# ark.net
KiCad netlist of a schematic drawn in Altium Designer
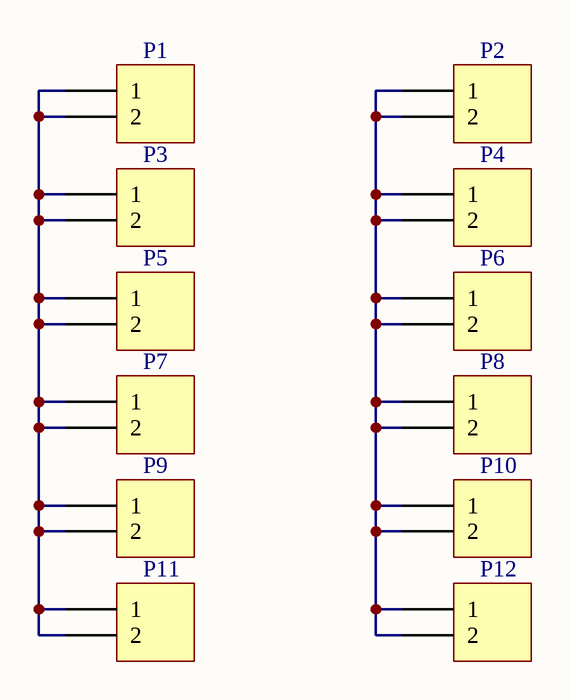
[diagram p0: ark.SchDoc]

(export (version "E")
  (design (tool "Eeschema 10.0.6"))
  (components
    (comp (ref "P1")
      (value "ARK 2-Pin")
      (footprint "ARK-5mm-2pin")
      (libsource (lib "Connectors") (part "ARK 2-Pin"))
    )
    (comp (ref "P2")
      (value "ARK 2-Pin")
      (footprint "ARK-5mm-2pin")
      (libsource (lib "Connectors") (part "ARK 2-Pin"))
    )
    (comp (ref "P3")
      (value "ARK 2-Pin")
      (footprint "ARK-5mm-2pin")
      (libsource (lib "Connectors") (part "ARK 2-Pin"))
    )
    (comp (ref "P4")
      (value "ARK 2-Pin")
      (footprint "ARK-5mm-2pin")
      (libsource (lib "Connectors") (part "ARK 2-Pin"))
    )
    (comp (ref "P5")
      (value "ARK 2-Pin")
      (footprint "ARK-5mm-2pin")
      (libsource (lib "Connectors") (part "ARK 2-Pin"))
    )
    (comp (ref "P6")
      (value "ARK 2-Pin")
      (footprint "ARK-5mm-2pin")
      (libsource (lib "Connectors") (part "ARK 2-Pin"))
    )
    (comp (ref "P7")
      (value "ARK 2-Pin")
      (footprint "ARK-5mm-2pin")
      (libsource (lib "Connectors") (part "ARK 2-Pin"))
    )
    (comp (ref "P8")
      (value "ARK 2-Pin")
      (footprint "ARK-5mm-2pin")
      (libsource (lib "Connectors") (part "ARK 2-Pin"))
    )
    (comp (ref "P9")
      (value "ARK 2-Pin")
      (footprint "ARK-5mm-2pin")
      (libsource (lib "Connectors") (part "ARK 2-Pin"))
    )
    (comp (ref "P10")
      (value "ARK 2-Pin")
      (footprint "ARK-5mm-2pin")
      (libsource (lib "Connectors") (part "ARK 2-Pin"))
    )
    (comp (ref "P11")
      (value "ARK 2-Pin")
      (footprint "ARK-5mm-2pin")
      (libsource (lib "Connectors") (part "ARK 2-Pin"))
    )
    (comp (ref "P12")
      (value "ARK 2-Pin")
      (footprint "ARK-5mm-2pin")
      (libsource (lib "Connectors") (part "ARK 2-Pin"))
    )
  )
  (nets
    (net (code "1") (name "Net-(P1-Pad1)") (class "Default")
      (node (ref "P1") (pin "1") (pinfunction "1_1") (pintype "passive"))
      (node (ref "P1") (pin "2") (pinfunction "2_2") (pintype "passive"))
      (node (ref "P11") (pin "1") (pinfunction "1_1") (pintype "passive"))
      (node (ref "P11") (pin "2") (pinfunction "2_2") (pintype "passive"))
      (node (ref "P3") (pin "1") (pinfunction "1_1") (pintype "passive"))
      (node (ref "P3") (pin "2") (pinfunction "2_2") (pintype "passive"))
      (node (ref "P5") (pin "1") (pinfunction "1_1") (pintype "passive"))
      (node (ref "P5") (pin "2") (pinfunction "2_2") (pintype "passive"))
      (node (ref "P7") (pin "1") (pinfunction "1_1") (pintype "passive"))
      (node (ref "P7") (pin "2") (pinfunction "2_2") (pintype "passive"))
      (node (ref "P9") (pin "1") (pinfunction "1_1") (pintype "passive"))
      (node (ref "P9") (pin "2") (pinfunction "2_2") (pintype "passive"))
    )
    (net (code "2") (name "Net-(P10-Pad1)") (class "Default")
      (node (ref "P10") (pin "1") (pinfunction "1_1") (pintype "passive"))
      (node (ref "P10") (pin "2") (pinfunction "2_2") (pintype "passive"))
      (node (ref "P12") (pin "1") (pinfunction "1_1") (pintype "passive"))
      (node (ref "P12") (pin "2") (pinfunction "2_2") (pintype "passive"))
      (node (ref "P2") (pin "1") (pinfunction "1_1") (pintype "passive"))
      (node (ref "P2") (pin "2") (pinfunction "2_2") (pintype "passive"))
      (node (ref "P4") (pin "1") (pinfunction "1_1") (pintype "passive"))
      (node (ref "P4") (pin "2") (pinfunction "2_2") (pintype "passive"))
      (node (ref "P6") (pin "1") (pinfunction "1_1") (pintype "passive"))
      (node (ref "P6") (pin "2") (pinfunction "2_2") (pintype "passive"))
      (node (ref "P8") (pin "1") (pinfunction "1_1") (pintype "passive"))
      (node (ref "P8") (pin "2") (pinfunction "2_2") (pintype "passive"))
    )
  )
)
